# Adafruit_HUZZAH_ESP8266_Basic_Breakout.net
KiCad netlist of a schematic drawn in EAGLE
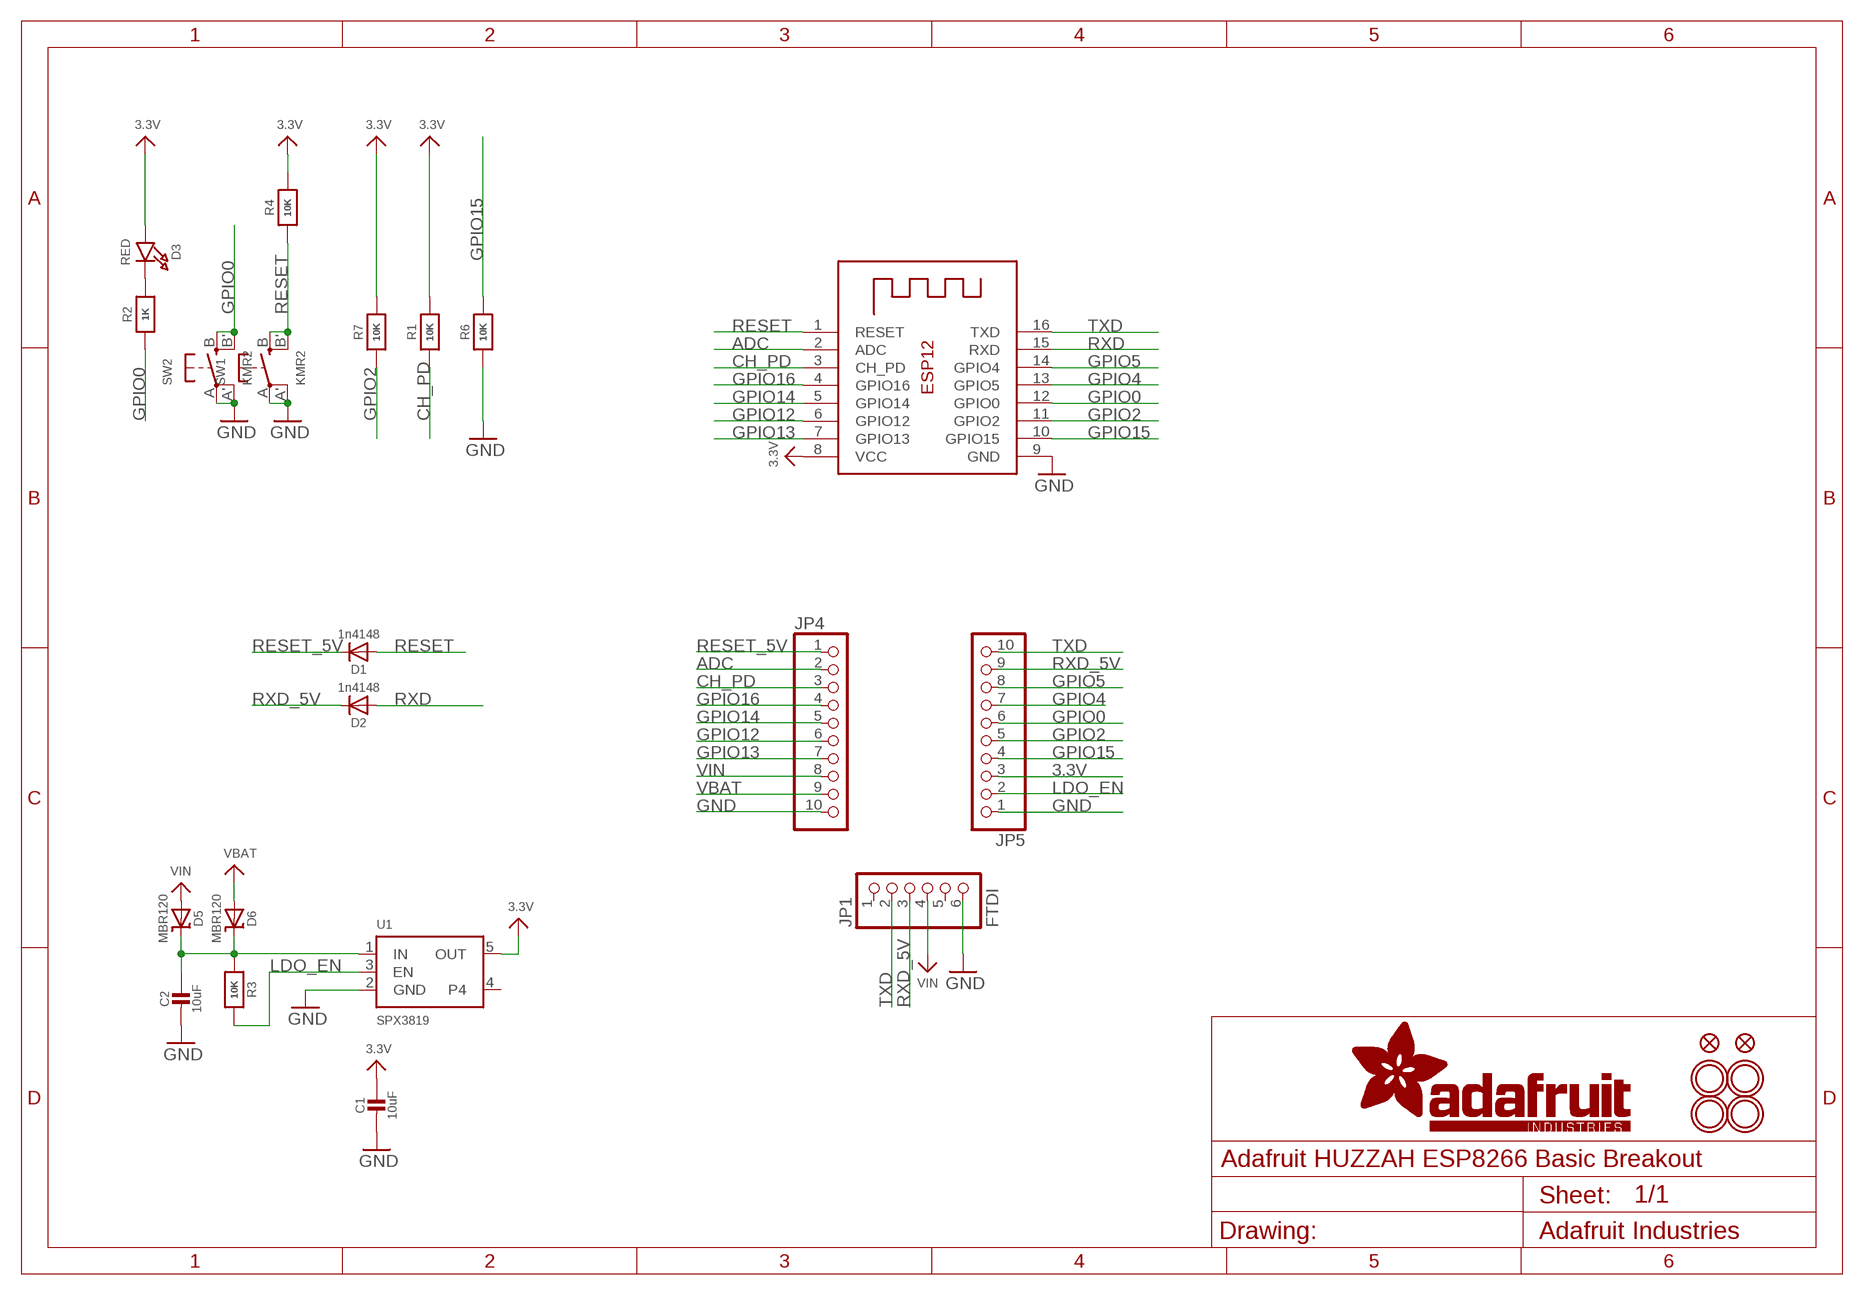
[diagram p0: schematic, sheet 1]

(export (version "E")
  (design (tool "Eeschema 10.0.6"))
  (components
    (comp (ref "C1")
      (value "10uF")
      (footprint "eagle-import:0805-NO")
      (libsource (lib "eagle-import") (part "CAP_CERAMIC0805-NOOUTLINE"))
    )
    (comp (ref "C2")
      (value "10uF")
      (footprint "eagle-import:0805-NO")
      (libsource (lib "eagle-import") (part "CAP_CERAMIC0805-NOOUTLINE"))
    )
    (comp (ref "D1")
      (value "1n4148")
      (footprint "eagle-import:SOD-323")
      (libsource (lib "eagle-import") (part "DIODESOD-323"))
    )
    (comp (ref "D2")
      (value "1n4148")
      (footprint "eagle-import:SOD-323")
      (libsource (lib "eagle-import") (part "DIODESOD-323"))
    )
    (comp (ref "D3")
      (value "RED")
      (footprint "eagle-import:CHIPLED_0805_NOOUTLINE")
      (libsource (lib "eagle-import") (part "LED0805_NOOUTLINE"))
    )
    (comp (ref "D5")
      (value "MBR120")
      (footprint "eagle-import:SOD-123")
      (libsource (lib "eagle-import") (part "DIODE-SCHOTTKYSOD-123"))
    )
    (comp (ref "D6")
      (value "MBR120")
      (footprint "eagle-import:SOD-123")
      (libsource (lib "eagle-import") (part "DIODE-SCHOTTKYSOD-123"))
    )
    (comp (ref "FID1")
      (value "FIDUCIAL\"\"")
      (footprint "eagle-import:FIDUCIAL_1MM")
      (libsource (lib "eagle-import") (part "FIDUCIAL{dblquote}{dblquote}"))
    )
    (comp (ref "FID3")
      (value "FIDUCIAL\"\"")
      (footprint "eagle-import:FIDUCIAL_1MM")
      (libsource (lib "eagle-import") (part "FIDUCIAL{dblquote}{dblquote}"))
    )
    (comp (ref "JP1")
      (value "FTDI")
      (footprint "eagle-import:1X06_ROUND_70")
      (libsource (lib "eagle-import") (part "HEADER-1X670MIL"))
    )
    (comp (ref "JP4")
      (value "HEADER-1X1070MIL")
      (footprint "eagle-import:1X10_ROUND70")
      (libsource (lib "eagle-import") (part "HEADER-1X1070MIL"))
    )
    (comp (ref "JP5")
      (value "HEADER-1X1070MIL")
      (footprint "eagle-import:1X10_ROUND70")
      (libsource (lib "eagle-import") (part "HEADER-1X1070MIL"))
    )
    (comp (ref "R1")
      (value "10K")
      (footprint "eagle-import:0805-NO")
      (libsource (lib "eagle-import") (part "RESISTOR0805_NOOUTLINE"))
    )
    (comp (ref "R2")
      (value "1K")
      (footprint "eagle-import:0805-NO")
      (libsource (lib "eagle-import") (part "RESISTOR0805_NOOUTLINE"))
    )
    (comp (ref "R3")
      (value "10K")
      (footprint "eagle-import:0805-NO")
      (libsource (lib "eagle-import") (part "RESISTOR0805_NOOUTLINE"))
    )
    (comp (ref "R4")
      (value "10K")
      (footprint "eagle-import:0805-NO")
      (libsource (lib "eagle-import") (part "RESISTOR0805_NOOUTLINE"))
    )
    (comp (ref "R6")
      (value "10K")
      (footprint "eagle-import:0805-NO")
      (libsource (lib "eagle-import") (part "RESISTOR0805_NOOUTLINE"))
    )
    (comp (ref "R7")
      (value "10K")
      (footprint "eagle-import:0805-NO")
      (libsource (lib "eagle-import") (part "RESISTOR0805_NOOUTLINE"))
    )
    (comp (ref "SW1")
      (value "KMR2")
      (footprint "eagle-import:BTN_KMR2_4.6X2.8")
      (libsource (lib "eagle-import") (part "SWITCH_TACT_SMT4.6X2.8"))
    )
    (comp (ref "SW2")
      (value "KMR2")
      (footprint "eagle-import:BTN_KMR2_4.6X2.8")
      (libsource (lib "eagle-import") (part "SWITCH_TACT_SMT4.6X2.8"))
    )
    (comp (ref "U$15")
      (value "MOUNTINGHOLE2.5")
      (footprint "eagle-import:MOUNTINGHOLE_2.5_PLATED")
      (libsource (lib "eagle-import") (part "MOUNTINGHOLE2.5"))
    )
    (comp (ref "U$16")
      (value "MOUNTINGHOLE2.5")
      (footprint "eagle-import:MOUNTINGHOLE_2.5_PLATED")
      (libsource (lib "eagle-import") (part "MOUNTINGHOLE2.5"))
    )
    (comp (ref "U$17")
      (value "MOUNTINGHOLE2.5")
      (footprint "eagle-import:MOUNTINGHOLE_2.5_PLATED")
      (libsource (lib "eagle-import") (part "MOUNTINGHOLE2.5"))
    )
    (comp (ref "U$18")
      (value "MOUNTINGHOLE2.5")
      (footprint "eagle-import:MOUNTINGHOLE_2.5_PLATED")
      (libsource (lib "eagle-import") (part "MOUNTINGHOLE2.5"))
    )
    (comp (ref "U1")
      (value "SPX3819")
      (footprint "eagle-import:SOT23-5")
      (libsource (lib "eagle-import") (part "VREG_SOT23-5"))
    )
    (comp (ref "X1")
      (value "ESP-12")
      (footprint "eagle-import:ESP-12")
      (libsource (lib "eagle-import") (part "ESP-12"))
    )
  )
  (nets
    (net (code "1") (name "/ADC") (class "Default")
      (node (ref "JP4") (pin "2") (pinfunction "2_2") (pintype "passive"))
      (node (ref "X1") (pin "2") (pinfunction "ADC_2") (pintype "passive"))
    )
    (net (code "2") (name "/CH_PD") (class "Default")
      (node (ref "JP4") (pin "3") (pinfunction "3_3") (pintype "passive"))
      (node (ref "R1") (pin "1") (pinfunction "1_1") (pintype "passive"))
      (node (ref "X1") (pin "3") (pinfunction "CH_PD_3") (pintype "input"))
    )
    (net (code "3") (name "/GPIO0") (class "Default")
      (node (ref "JP5") (pin "6") (pinfunction "6_6") (pintype "passive"))
      (node (ref "R2") (pin "1") (pinfunction "1_1") (pintype "passive"))
      (node (ref "SW2") (pin "B") (pinfunction "S_B") (pintype "passive"))
      (node (ref "SW2") (pin "B'") (pinfunction "S1_B'") (pintype "passive"))
      (node (ref "X1") (pin "12") (pinfunction "GPIO0_12") (pintype "bidirectional"))
    )
    (net (code "4") (name "/GPIO2") (class "Default")
      (node (ref "JP5") (pin "5") (pinfunction "5_5") (pintype "passive"))
      (node (ref "R7") (pin "1") (pinfunction "1_1") (pintype "passive"))
      (node (ref "X1") (pin "11") (pinfunction "GPIO2_11") (pintype "bidirectional"))
    )
    (net (code "5") (name "/GPIO4") (class "Default")
      (node (ref "JP5") (pin "7") (pinfunction "7_7") (pintype "passive"))
      (node (ref "X1") (pin "13") (pinfunction "GPIO5_13") (pintype "bidirectional"))
    )
    (net (code "6") (name "/GPIO5") (class "Default")
      (node (ref "JP5") (pin "8") (pinfunction "8_8") (pintype "passive"))
      (node (ref "X1") (pin "14") (pinfunction "GPIO4_14") (pintype "bidirectional"))
    )
    (net (code "7") (name "/GPIO12") (class "Default")
      (node (ref "JP4") (pin "6") (pinfunction "6_6") (pintype "passive"))
      (node (ref "X1") (pin "6") (pinfunction "GPIO12_6") (pintype "bidirectional"))
    )
    (net (code "8") (name "/GPIO13") (class "Default")
      (node (ref "JP4") (pin "7") (pinfunction "7_7") (pintype "passive"))
      (node (ref "X1") (pin "7") (pinfunction "GPIO13_7") (pintype "bidirectional"))
    )
    (net (code "9") (name "/GPIO14") (class "Default")
      (node (ref "JP4") (pin "5") (pinfunction "5_5") (pintype "passive"))
      (node (ref "X1") (pin "5") (pinfunction "GPIO14_5") (pintype "bidirectional"))
    )
    (net (code "10") (name "/GPIO15") (class "Default")
      (node (ref "JP5") (pin "4") (pinfunction "4_4") (pintype "passive"))
      (node (ref "R6") (pin "2") (pinfunction "2_2") (pintype "passive"))
      (node (ref "X1") (pin "10") (pinfunction "GPIO15_10") (pintype "bidirectional"))
    )
    (net (code "11") (name "/GPIO16") (class "Default")
      (node (ref "JP4") (pin "4") (pinfunction "4_4") (pintype "passive"))
      (node (ref "X1") (pin "4") (pinfunction "GPIO16_4") (pintype "bidirectional"))
    )
    (net (code "12") (name "/LDO_EN") (class "Default")
      (node (ref "JP5") (pin "2") (pinfunction "2_2") (pintype "passive"))
      (node (ref "R3") (pin "2") (pinfunction "2_2") (pintype "passive"))
      (node (ref "U1") (pin "3") (pinfunction "EN_3") (pintype "input"))
    )
    (net (code "13") (name "/RESET") (class "Default")
      (node (ref "D1") (pin "A") (pinfunction "A_A") (pintype "passive"))
      (node (ref "R4") (pin "1") (pinfunction "1_1") (pintype "passive"))
      (node (ref "SW1") (pin "B") (pinfunction "S_B") (pintype "passive"))
      (node (ref "SW1") (pin "B'") (pinfunction "S1_B'") (pintype "passive"))
      (node (ref "X1") (pin "1") (pinfunction "RESET_1") (pintype "input"))
    )
    (net (code "14") (name "/RESET_5V") (class "Default")
      (node (ref "D1") (pin "C") (pinfunction "C_C") (pintype "passive"))
      (node (ref "JP4") (pin "1") (pinfunction "1_1") (pintype "passive"))
    )
    (net (code "15") (name "/RXD") (class "Default")
      (node (ref "D2") (pin "A") (pinfunction "A_A") (pintype "passive"))
      (node (ref "X1") (pin "15") (pinfunction "RXD_15") (pintype "input"))
    )
    (net (code "16") (name "/RXD_5V") (class "Default")
      (node (ref "D2") (pin "C") (pinfunction "C_C") (pintype "passive"))
      (node (ref "JP1") (pin "3") (pinfunction "3_3") (pintype "passive"))
      (node (ref "JP5") (pin "9") (pinfunction "9_9") (pintype "passive"))
    )
    (net (code "17") (name "/TXD") (class "Default")
      (node (ref "JP1") (pin "2") (pinfunction "2_2") (pintype "passive"))
      (node (ref "JP5") (pin "10") (pinfunction "10_10") (pintype "passive"))
      (node (ref "X1") (pin "16") (pinfunction "TXD_16") (pintype "output"))
    )
    (net (code "18") (name "3.3V") (class "Default")
      (node (ref "C1") (pin "1") (pinfunction "1_1") (pintype "passive"))
      (node (ref "D3") (pin "A") (pinfunction "A_A") (pintype "passive"))
      (node (ref "JP5") (pin "3") (pinfunction "3_3") (pintype "passive"))
      (node (ref "R1") (pin "2") (pinfunction "2_2") (pintype "passive"))
      (node (ref "R4") (pin "2") (pinfunction "2_2") (pintype "passive"))
      (node (ref "R7") (pin "2") (pinfunction "2_2") (pintype "passive"))
      (node (ref "U1") (pin "5") (pinfunction "OUT_5") (pintype "power_in"))
      (node (ref "X1") (pin "8") (pinfunction "VCC_8") (pintype "power_in"))
    )
    (net (code "19") (name "GND") (class "Default")
      (node (ref "C1") (pin "2") (pinfunction "2_2") (pintype "passive"))
      (node (ref "C2") (pin "2") (pinfunction "2_2") (pintype "passive"))
      (node (ref "JP1") (pin "6") (pinfunction "6_6") (pintype "passive"))
      (node (ref "JP4") (pin "10") (pinfunction "10_10") (pintype "passive"))
      (node (ref "JP5") (pin "1") (pinfunction "1_1") (pintype "passive"))
      (node (ref "R6") (pin "1") (pinfunction "1_1") (pintype "passive"))
      (node (ref "SW1") (pin "A") (pinfunction "P_A") (pintype "passive"))
      (node (ref "SW1") (pin "A'") (pinfunction "P1_A'") (pintype "passive"))
      (node (ref "SW2") (pin "A") (pinfunction "P_A") (pintype "passive"))
      (node (ref "SW2") (pin "A'") (pinfunction "P1_A'") (pintype "passive"))
      (node (ref "U1") (pin "2") (pinfunction "GND_2") (pintype "power_in"))
      (node (ref "X1") (pin "9") (pinfunction "GND_9") (pintype "power_in"))
    )
    (net (code "20") (name "Net-(D3-PadC)") (class "Default")
      (node (ref "D3") (pin "C") (pinfunction "C_C") (pintype "passive"))
      (node (ref "R2") (pin "2") (pinfunction "2_2") (pintype "passive"))
    )
    (net (code "21") (name "Net-(U1-IN)") (class "Default")
      (node (ref "C2") (pin "1") (pinfunction "1_1") (pintype "passive"))
      (node (ref "D5") (pin "C") (pinfunction "C_C") (pintype "passive"))
      (node (ref "D6") (pin "C") (pinfunction "C_C") (pintype "passive"))
      (node (ref "R3") (pin "1") (pinfunction "1_1") (pintype "passive"))
      (node (ref "U1") (pin "1") (pinfunction "IN_1") (pintype "power_in"))
    )
    (net (code "22") (name "VBAT") (class "Default")
      (node (ref "D6") (pin "A") (pinfunction "A_A") (pintype "passive"))
      (node (ref "JP4") (pin "9") (pinfunction "9_9") (pintype "passive"))
    )
    (net (code "23") (name "VIN") (class "Default")
      (node (ref "D5") (pin "A") (pinfunction "A_A") (pintype "passive"))
      (node (ref "JP1") (pin "4") (pinfunction "4_4") (pintype "passive"))
      (node (ref "JP4") (pin "8") (pinfunction "8_8") (pintype "passive"))
    )
    (net (code "24") (name "unconnected-(JP1-Pad1)") (class "Default")
      (node (ref "JP1") (pin "1") (pinfunction "1_1") (pintype "passive"))
    )
    (net (code "25") (name "unconnected-(JP1-Pad5)") (class "Default")
      (node (ref "JP1") (pin "5") (pinfunction "5_5") (pintype "passive"))
    )
    (net (code "26") (name "unconnected-(U1-P4-Pad4)") (class "Default")
      (node (ref "U1") (pin "4") (pinfunction "P4_4") (pintype "bidirectional"))
    )
  )
)
